# mainboard_wifi_v1_3.net
KiCad netlist of a schematic drawn in Altium Designer
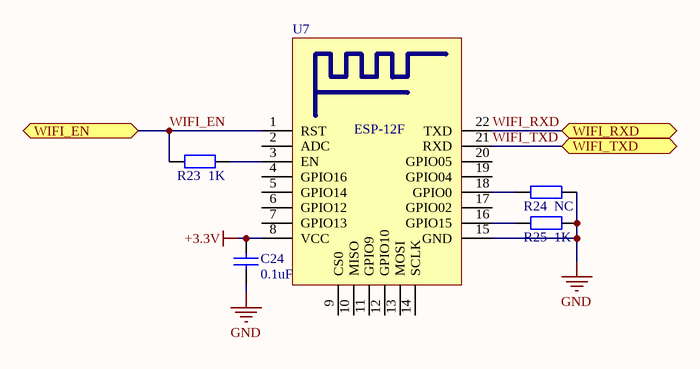
[diagram p0: mainboard_wifi.v1.3.SchDoc]

(export (version "E")
  (design (tool "Eeschema 10.0.6"))
  (components
    (comp (ref "C24")
      (value "0.1uF")
      (footprint "0805")
      (description "Capacitor")
      (libsource (lib "Miscellaneous Devices") (part "Cap"))
    )
    (comp (ref "R23")
      (value "1K")
      (footprint "0805")
      (description "Resistor")
      (libsource (lib "Miscellaneous Devices") (part "Res2"))
    )
    (comp (ref "R24")
      (value "NC")
      (footprint "0805")
      (description "Resistor")
      (libsource (lib "Miscellaneous Devices") (part "Res2"))
    )
    (comp (ref "R25")
      (value "1K")
      (footprint "0805")
      (description "Resistor")
      (libsource (lib "Miscellaneous Devices") (part "Res2"))
    )
    (comp (ref "U7") (value "ESP-12F") (footprint "ESP-12F") (libsource (lib "Componet") (part "ESP-12F")))
  )
  (nets
    (net (code "1") (name "+3.3V") (class "Default")
      (node (ref "C24") (pin "2") (pinfunction "2_2") (pintype "passive"))
      (node (ref "U7") (pin "8") (pinfunction "VCC_8") (pintype "passive"))
    )
    (net (code "2") (name "/WIFI_EN") (class "Default")
      (node (ref "R23") (pin "1") (pinfunction "1_1") (pintype "passive"))
      (node (ref "U7") (pin "1") (pinfunction "RST_1") (pintype "passive"))
    )
    (net (code "3") (name "/WIFI_RXD") (class "Default")
      (node (ref "U7") (pin "22") (pinfunction "TXD_22") (pintype "passive"))
    )
    (net (code "4") (name "/WIFI_TXD") (class "Default")
      (node (ref "U7") (pin "21") (pinfunction "RXD_21") (pintype "passive"))
    )
    (net (code "5") (name "GND") (class "Default")
      (node (ref "C24") (pin "1") (pinfunction "1_1") (pintype "passive"))
      (node (ref "R24") (pin "2") (pinfunction "2_2") (pintype "passive"))
      (node (ref "R25") (pin "2") (pinfunction "2_2") (pintype "passive"))
      (node (ref "U7") (pin "15") (pinfunction "GND_15") (pintype "passive"))
    )
    (net (code "6") (name "Net-(U7-EN)") (class "Default")
      (node (ref "R23") (pin "2") (pinfunction "2_2") (pintype "passive"))
      (node (ref "U7") (pin "3") (pinfunction "EN_3") (pintype "passive"))
    )
    (net (code "7") (name "Net-(U7-GPIO0)") (class "Default")
      (node (ref "R24") (pin "1") (pinfunction "1_1") (pintype "passive"))
      (node (ref "U7") (pin "18") (pinfunction "GPIO0_18") (pintype "passive"))
    )
    (net (code "8") (name "Net-(U7-GPIO15)") (class "Default")
      (node (ref "R25") (pin "1") (pinfunction "1_1") (pintype "passive"))
      (node (ref "U7") (pin "16") (pinfunction "GPIO15_16") (pintype "passive"))
    )
    (net (code "9") (name "unconnected-(U7-ADC-Pad2)") (class "Default")
      (node (ref "U7") (pin "2") (pinfunction "ADC_2") (pintype "passive"))
    )
    (net (code "10") (name "unconnected-(U7-CS0-Pad9)") (class "Default")
      (node (ref "U7") (pin "9") (pinfunction "CS0_9") (pintype "passive"))
    )
    (net (code "11") (name "unconnected-(U7-GPIO02-Pad17)") (class "Default")
      (node (ref "U7") (pin "17") (pinfunction "GPIO02_17") (pintype "passive"))
    )
    (net (code "12") (name "unconnected-(U7-GPIO04-Pad19)") (class "Default")
      (node (ref "U7") (pin "19") (pinfunction "GPIO04_19") (pintype "passive"))
    )
    (net (code "13") (name "unconnected-(U7-GPIO05-Pad20)") (class "Default")
      (node (ref "U7") (pin "20") (pinfunction "GPIO05_20") (pintype "passive"))
    )
    (net (code "14") (name "unconnected-(U7-GPIO9-Pad11)") (class "Default")
      (node (ref "U7") (pin "11") (pinfunction "GPIO9_11") (pintype "passive"))
    )
    (net (code "15") (name "unconnected-(U7-GPIO10-Pad12)") (class "Default")
      (node (ref "U7") (pin "12") (pinfunction "GPIO10_12") (pintype "passive"))
    )
    (net (code "16") (name "unconnected-(U7-GPIO12-Pad6)") (class "Default")
      (node (ref "U7") (pin "6") (pinfunction "GPIO12_6") (pintype "passive"))
    )
    (net (code "17") (name "unconnected-(U7-GPIO13-Pad7)") (class "Default")
      (node (ref "U7") (pin "7") (pinfunction "GPIO13_7") (pintype "passive"))
    )
    (net (code "18") (name "unconnected-(U7-GPIO14-Pad5)") (class "Default")
      (node (ref "U7") (pin "5") (pinfunction "GPIO14_5") (pintype "passive"))
    )
    (net (code "19") (name "unconnected-(U7-GPIO16-Pad4)") (class "Default")
      (node (ref "U7") (pin "4") (pinfunction "GPIO16_4") (pintype "passive"))
    )
    (net (code "20") (name "unconnected-(U7-MISO-Pad10)") (class "Default")
      (node (ref "U7") (pin "10") (pinfunction "MISO_10") (pintype "passive"))
    )
    (net (code "21") (name "unconnected-(U7-MOSI-Pad13)") (class "Default")
      (node (ref "U7") (pin "13") (pinfunction "MOSI_13") (pintype "passive"))
    )
    (net (code "22") (name "unconnected-(U7-SCLK-Pad14)") (class "Default")
      (node (ref "U7") (pin "14") (pinfunction "SCLK_14") (pintype "passive"))
    )
  )
)
